# SCH_WINGLET_GNSS.net
KiCad netlist of a schematic drawn in Altium Designer
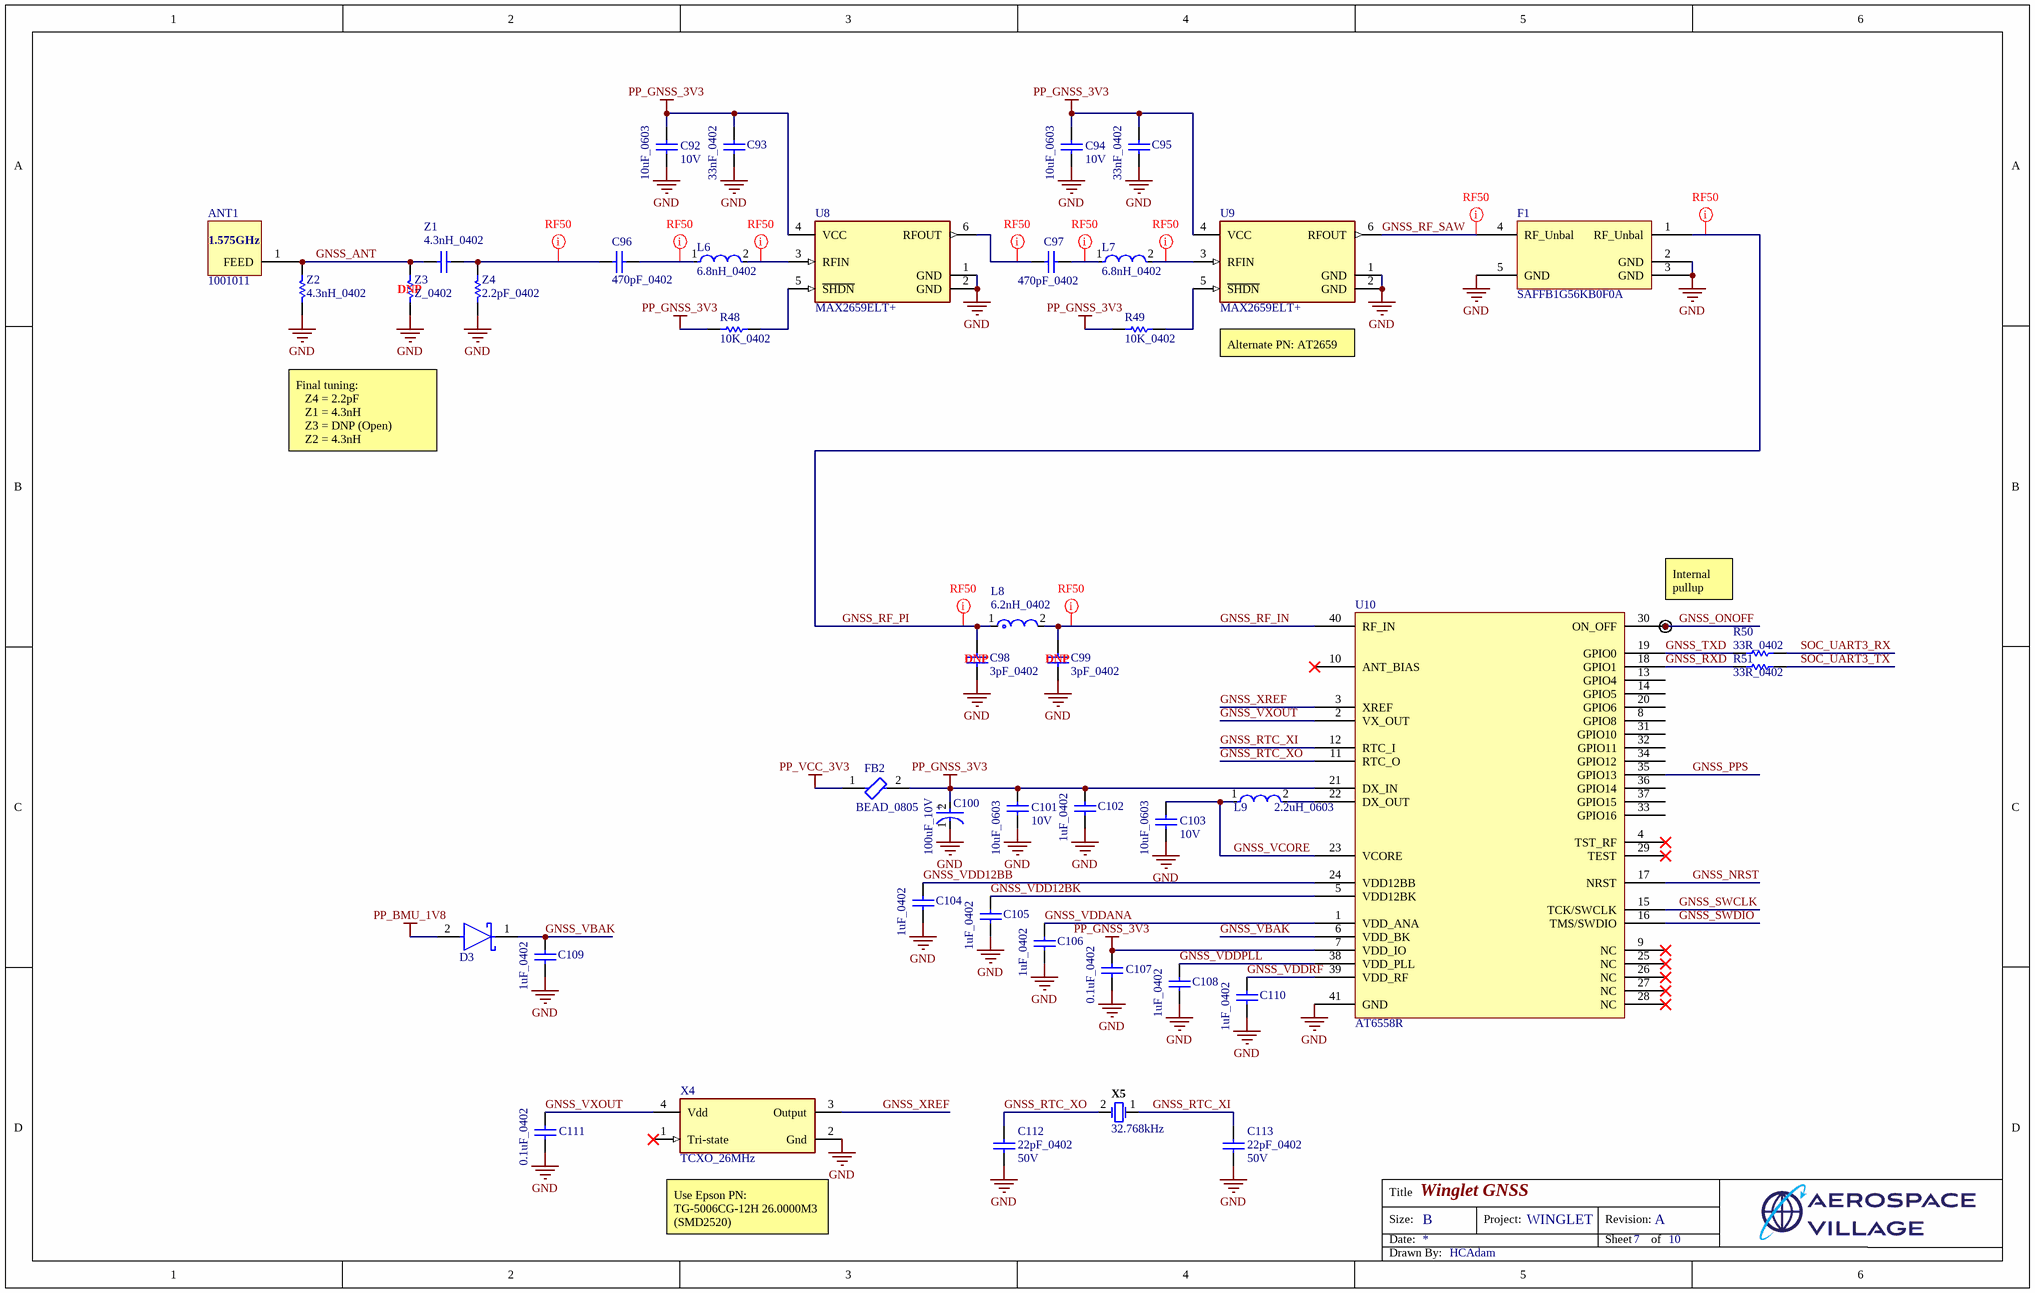
[diagram p0: SCH_WINGLET_GNSS.SchDoc]

(export (version "E")
  (design (tool "Eeschema 10.0.6"))
  (components
    (comp (ref "ANT1")
      (value "1001011")
      (footprint "ANT1001011")
      (libsource (lib "DCAV32_WINGLET_SCHLIB") (part "1001011"))
    )
    (comp (ref "C92")
      (value "10uF_0603")
      (footprint "CAPC1609X100X15NL20")
      (fields
        (field (name "PART NUMBER") "TACL106M006XTA")
        (field (name "MANUFACTURER") "AVX Interconnect / Elco")
        (field (name "VOLTAGE RATING") "10V")
      )
      (libsource (lib "Altium Content Vault") (part "CAP"))
    )
    (comp (ref "C93")
      (value "33nF_0402")
      (footprint "CAPC1005X56X25NL10T15")
      (libsource (lib "Altium Content Vault") (part "CAP"))
    )
    (comp (ref "C94")
      (value "10uF_0603")
      (footprint "CAPC1609X100X15NL20")
      (fields
        (field (name "PART NUMBER") "TACL106M006XTA")
        (field (name "MANUFACTURER") "AVX Interconnect / Elco")
        (field (name "VOLTAGE RATING") "10V")
      )
      (libsource (lib "Altium Content Vault") (part "CAP"))
    )
    (comp (ref "C95")
      (value "33nF_0402")
      (footprint "CAPC1005X56X25NL10T15")
      (libsource (lib "Altium Content Vault") (part "CAP"))
    )
    (comp (ref "C96")
      (value "470pF_0402")
      (footprint "CAPC1005X56X25NL10T15")
      (libsource (lib "Altium Content Vault") (part "CAP"))
    )
    (comp (ref "C97")
      (value "470pF_0402")
      (footprint "CAPC1005X56X25NL10T15")
      (libsource (lib "Altium Content Vault") (part "CAP"))
    )
    (comp (ref "C98")
      (value "3pF_0402")
      (footprint "CAPC1005X55X25NL05T10")
      (description "GRM1555C1H3R0BA01D")
      (fields (field (name "MANUFACTURER") "Murata") (field (name "DNP") "DNP"))
      (libsource (lib "Altium Content Vault") (part "CAP"))
    )
    (comp (ref "C99")
      (value "3pF_0402")
      (footprint "CAPC1005X55X25NL05T10")
      (description "GRM1555C1H3R0BA01D")
      (fields (field (name "MANUFACTURER") "Murata") (field (name "DNP") "DNP"))
      (libsource (lib "Altium Content Vault") (part "CAP"))
    )
    (comp (ref "C100")
      (value "100uF_10V")
      (footprint "FP-TAJB-MFG")
      (description "100uF 10V ±10% 1.7Ω SMD CASE-B (3528) Tantalum Capacitor")
      (fields (field (name "VOLTAGE") "6.3V") (field (name "TOLERANCE") "10%"))
      (libsource (lib "Altium Content Vault") (part "203bc49f2ac43e59fd269a8c329ed05"))
    )
    (comp (ref "C101")
      (value "10uF_0603")
      (footprint "CAPC1609X100X15NL20")
      (fields
        (field (name "PART NUMBER") "TACL106M006XTA")
        (field (name "MANUFACTURER") "AVX Interconnect / Elco")
        (field (name "VOLTAGE RATING") "10V")
      )
      (libsource (lib "Altium Content Vault") (part "CAP"))
    )
    (comp (ref "C102")
      (value "1uF_0402")
      (footprint "CAPC1005X55X25NL5T10")
      (fields (field (name "TOLERANCE") "10%") (field (name "PARTNUMBER") "GRM155R60J105KE19D"))
      (libsource (lib "Altium Content Vault") (part "CAP-NP-2"))
    )
    (comp (ref "C103")
      (value "10uF_0603")
      (footprint "CAPC1609X100X15NL20")
      (fields
        (field (name "PART NUMBER") "TACL106M006XTA")
        (field (name "MANUFACTURER") "AVX Interconnect / Elco")
        (field (name "VOLTAGE RATING") "10V")
      )
      (libsource (lib "Altium Content Vault") (part "CAP"))
    )
    (comp (ref "C104")
      (value "1uF_0402")
      (footprint "CAPC1005X55X25NL5T10")
      (fields (field (name "TOLERANCE") "10%") (field (name "PARTNUMBER") "GRM155R60J105KE19D"))
      (libsource (lib "Altium Content Vault") (part "CAP-NP-2"))
    )
    (comp (ref "C105")
      (value "1uF_0402")
      (footprint "CAPC1005X55X25NL5T10")
      (fields (field (name "TOLERANCE") "10%") (field (name "PARTNUMBER") "GRM155R60J105KE19D"))
      (libsource (lib "Altium Content Vault") (part "CAP-NP-2"))
    )
    (comp (ref "C106")
      (value "1uF_0402")
      (footprint "CAPC1005X55X25NL5T10")
      (fields (field (name "TOLERANCE") "10%") (field (name "PARTNUMBER") "GRM155R60J105KE19D"))
      (libsource (lib "Altium Content Vault") (part "CAP-NP-2"))
    )
    (comp (ref "C107")
      (value "0.1uF_0402")
      (footprint "CAPC1005X56X25NL10T15")
      (description "04026D104KAT2A")
      (fields (field (name "MANUFACTURER") "AVX Interconnect / Elco"))
      (libsource (lib "Altium Content Vault") (part "CAP"))
    )
    (comp (ref "C108")
      (value "1uF_0402")
      (footprint "CAPC1005X55X25NL5T10")
      (fields (field (name "TOLERANCE") "10%") (field (name "PARTNUMBER") "GRM155R60J105KE19D"))
      (libsource (lib "Altium Content Vault") (part "CAP-NP-2"))
    )
    (comp (ref "C109")
      (value "1uF_0402")
      (footprint "CAPC1005X55X25NL5T10")
      (fields (field (name "TOLERANCE") "10%") (field (name "PARTNUMBER") "GRM155R60J105KE19D"))
      (libsource (lib "Altium Content Vault") (part "CAP-NP-2"))
    )
    (comp (ref "C110")
      (value "1uF_0402")
      (footprint "CAPC1005X55X25NL5T10")
      (fields (field (name "TOLERANCE") "10%") (field (name "PARTNUMBER") "GRM155R60J105KE19D"))
      (libsource (lib "Altium Content Vault") (part "CAP-NP-2"))
    )
    (comp (ref "C111")
      (value "0.1uF_0402")
      (footprint "CAPC1005X56X25NL10T15")
      (description "04026D104KAT2A")
      (fields (field (name "MANUFACTURER") "AVX Interconnect / Elco"))
      (libsource (lib "Altium Content Vault") (part "CAP"))
    )
    (comp (ref "C112")
      (value "22pF_0402")
      (footprint "CAPC1005X56X25LL10T15")
      (description "04025A220JAT2A")
      (fields (field (name "MANUFACTURER") "AVX Interconnect / Elco") (field (name "VOLTAGE RATING") "50V"))
      (libsource (lib "Altium Content Vault") (part "CAP"))
    )
    (comp (ref "C113")
      (value "22pF_0402")
      (footprint "CAPC1005X56X25LL10T15")
      (description "04025A220JAT2A")
      (fields (field (name "MANUFACTURER") "AVX Interconnect / Elco") (field (name "VOLTAGE RATING") "50V"))
      (libsource (lib "Altium Content Vault") (part "CAP"))
    )
    (comp (ref "D3")
      (value "BAT54KFILM")
      (footprint "FP-SOD-523-MFG")
      (description "DIODE SCHOTTKY 40V 300MA SOD523")
      (fields
        (field (name "OCTOPART") "https://octopart.com/bat54kfilm-stmicroelectronics-39618022")
        (field (name "MANUFACTURER") "STMicroelectronics")
      )
      (libsource (lib "Altium Content Vault") (part "1d6ec82d83fb6aee721767c19dac4b9"))
    )
    (comp (ref "F1")
      (value "SAFFB1G56KB0F0A")
      (footprint "SAW80P110X50-5L")
      (description "SAW FILTER FOR GPS/GLONASS/BEIDOU2\r\n1561.10/1575.42/1602 MHz")
      (libsource (lib "DCAV32_WINGLET_SCHLIB") (part "SAFFB1G56KB0F0A"))
    )
    (comp (ref "FB2")
      (value "BEAD_0805")
      (footprint "FP-BLM21-0_2-t0_85-e0_5-IPC_B")
      (description "Chip Ferrite Bead, 0805, 150Ω @ 100MHz, 0.09Ω, 25%, 1A")
      (fields (field (name "TOLERANCE") "25%"))
      (libsource (lib "Altium Content Vault") (part "5f30dd21d616792df468990f7003faa"))
    )
    (comp (ref "L6")
      (value "6.8nH_0402")
      (footprint "FP-LQW15AN_00-W0_6-0_1-MFG")
      (description "Wire Wound RF Inductor 6.8nH ±3% 700mA 0.09Ω 0402 (1005)\r\nLQW15AN6N8H00D")
      (fields (field (name "TOLERANCE") "3%"))
      (libsource (lib "Altium Content Vault") (part "725321dda6339637d4d059423bc1c3c"))
    )
    (comp (ref "L7")
      (value "6.8nH_0402")
      (footprint "FP-LQW15AN_00-W0_6-0_1-MFG")
      (description "Wire Wound RF Inductor 6.8nH ±3% 700mA 0.09Ω 0402 (1005)\r\nLQW15AN6N8H00D")
      (fields (field (name "TOLERANCE") "3%"))
      (libsource (lib "Altium Content Vault") (part "725321dda6339637d4d059423bc1c3c"))
    )
    (comp (ref "L8")
      (value "6.2nH_0402")
      (footprint "FP-LQG15HH_02-IPC_C")
      (description "Multilayer type RF Inductor 6.2nH ±0.3nH 0.19Ω 600mA 0402\r\nLQG15HN6N2S02D")
      (libsource (lib "Altium Content Vault") (part "4cc4b267dca4c8e51f7102f422741d8"))
    )
    (comp (ref "L9")
      (value "2.2uH_0603")
      (footprint "FP-MLZ1608-IPC_C")
      (description "Shielded Multilayer Inductor 2.2uH ±20% 500mA 234mΩ SMD 0603\r\nMLZ1608N2R2LT000")
      (fields (field (name "TOLERANCE") "20%"))
      (libsource (lib "Altium Content Vault") (part "725321dda6339637d4d059423bc1c3c"))
    )
    (comp (ref "R48")
      (value "10K_0402")
      (footprint "RESC1005X40X25NL05T05")
      (fields (field (name "TOLERANCE") "1%") (field (name "MANUFACTURER") "Panasonic"))
      (libsource (lib "Altium Content Vault") (part "RES-2"))
    )
    (comp (ref "R49")
      (value "10K_0402")
      (footprint "RESC1005X40X25NL05T05")
      (fields (field (name "TOLERANCE") "1%") (field (name "MANUFACTURER") "Panasonic"))
      (libsource (lib "Altium Content Vault") (part "RES-2"))
    )
    (comp (ref "R50")
      (value "33R_0402")
      (footprint "RESC1005X40X25NL05T05")
      (description "ERJ2RKF33R0X")
      (fields (field (name "MANUFACTURER") "Panasonic"))
      (libsource (lib "Altium Content Vault") (part "RES"))
    )
    (comp (ref "R51")
      (value "33R_0402")
      (footprint "RESC1005X40X25NL05T05")
      (description "ERJ2RKF33R0X")
      (fields (field (name "MANUFACTURER") "Panasonic"))
      (libsource (lib "Altium Content Vault") (part "RES"))
    )
    (comp (ref "TP27")
      (value "TESTPOINT")
      (footprint "TESTPOINT-0.7MM-SINGLE-LAYER")
      (description "TESTPOINT SINGLE LAYER 0.7MM")
      (libsource (lib "DCAV32_WINGLET_SCHLIB") (part "TP_07"))
    )
    (comp (ref "U8")
      (value "MAX2659ELT+")
      (footprint "FP-L611-2-MFG")
      (description "GPS Amp Single Low Noise 1.75GHz 3.6V 6-Pin UDFN")
      (libsource (lib "Altium Content Vault") (part "fca23d189b6920f08195121cb41012b"))
    )
    (comp (ref "U9")
      (value "MAX2659ELT+")
      (footprint "FP-L611-2-MFG")
      (description "GPS Amp Single Low Noise 1.75GHz 3.6V 6-Pin UDFN")
      (libsource (lib "Altium Content Vault") (part "fca23d189b6920f08195121cb41012b"))
    )
    (comp (ref "U10")
      (value "AT6558R")
      (footprint "QFN40P500X500X90_HS-41N")
      (description "GNSS/BDS Satellite Positioning SOC")
      (libsource (lib "DCAV32_WINGLET_SCHLIB") (part "AT6558R"))
    )
    (comp (ref "X4")
      (value "TCXO_26MHz")
      (footprint "FP-ECS-TXO-2520-MFG")
      (description "XTAL OSC TCXO 25.0000MHZ HCMOS\r\n!!! SUBSTITUTE !!!")
      (libsource (lib "Altium Content Vault") (part "04cd953f3cf158082f8c09fbdb924ef"))
    )
    (comp (ref "X5")
      (value "32.768kHz")
      (footprint "ABRA-ABS07_A_V")
      (fields (field (name "MANUFACTURER") "Abracon") (field (name "TOLERANCE") "20ppm"))
      (libsource (lib "Altium Content Vault") (part "XTAL-1-2-2"))
    )
    (comp (ref "Z1")
      (value "4.3nH_0402")
      (footprint "CAPC1006X50X20NL10T10")
      (description "04023J1R6ABSTR")
      (fields (field (name "MANUFACTURER") "AVX Interconnect / Elco"))
      (libsource (lib "Altium Content Vault") (part "CAP"))
    )
    (comp (ref "Z2")
      (value "4.3nH_0402")
      (footprint "RESC1005X40X25NL05T05")
      (fields (field (name "TOLERANCE") "1%") (field (name "MANUFACTURER") "Panasonic"))
      (libsource (lib "Altium Content Vault") (part "RES-2"))
    )
    (comp (ref "Z3")
      (value "Z_0402")
      (footprint "RESC1005X40X25NL05T05")
      (fields
        (field (name "TOLERANCE") "1%")
        (field (name "MANUFACTURER") "Panasonic")
        (field (name "DNP") "DNP")
      )
      (libsource (lib "Altium Content Vault") (part "RES-2"))
    )
    (comp (ref "Z4")
      (value "2.2pF_0402")
      (footprint "RESC1005X40X25NL05T05")
      (fields (field (name "TOLERANCE") "1%") (field (name "MANUFACTURER") "Panasonic"))
      (libsource (lib "Altium Content Vault") (part "RES-2"))
    )
  )
  (nets
    (net (code "1") (name "/GNSS_ANT") (class "Default")
      (node (ref "ANT1") (pin "1") (pinfunction "FEED_1") (pintype "passive"))
      (node (ref "Z1") (pin "2") (pinfunction "2_2") (pintype "passive"))
      (node (ref "Z2") (pin "2") (pinfunction "2_2") (pintype "passive"))
      (node (ref "Z3") (pin "2") (pinfunction "2_2") (pintype "passive"))
    )
    (net (code "2") (name "/GNSS_NRST") (class "Default")
      (node (ref "U10") (pin "17") (pinfunction "NRST_17") (pintype "passive"))
    )
    (net (code "3") (name "/GNSS_ONOFF") (class "Default")
      (node (ref "TP27") (pin "1") (pinfunction "1_1") (pintype "passive"))
      (node (ref "U10") (pin "30") (pinfunction "ON_OFF_30") (pintype "passive"))
    )
    (net (code "4") (name "/GNSS_PPS") (class "Default")
      (node (ref "U10") (pin "35") (pinfunction "GPIO13_35") (pintype "passive"))
    )
    (net (code "5") (name "/GNSS_RF_IN") (class "Default")
      (node (ref "C99") (pin "2") (pinfunction "2_2") (pintype "passive"))
      (node (ref "L8") (pin "2") (pinfunction "2_2") (pintype "passive"))
      (node (ref "U10") (pin "40") (pinfunction "RF_IN_40") (pintype "passive"))
    )
    (net (code "6") (name "/GNSS_RF_PI") (class "Default")
      (node (ref "C98") (pin "2") (pinfunction "2_2") (pintype "passive"))
      (node (ref "F1") (pin "1") (pinfunction "RF_Unbal_1") (pintype "passive"))
      (node (ref "L8") (pin "1") (pinfunction "1_1") (pintype "passive"))
    )
    (net (code "7") (name "/GNSS_RF_SAW") (class "Default")
      (node (ref "F1") (pin "4") (pinfunction "RF_Unbal_4") (pintype "passive"))
      (node (ref "U9") (pin "6") (pinfunction "RFOUT_6") (pintype "output"))
    )
    (net (code "8") (name "/GNSS_RTC_XI") (class "Default")
      (node (ref "C113") (pin "2") (pinfunction "2_2") (pintype "passive"))
      (node (ref "U10") (pin "12") (pinfunction "RTC_I_12") (pintype "passive"))
      (node (ref "X5") (pin "1") (pinfunction "1_1") (pintype "passive"))
    )
    (net (code "9") (name "/GNSS_RTC_XO") (class "Default")
      (node (ref "C112") (pin "2") (pinfunction "2_2") (pintype "passive"))
      (node (ref "U10") (pin "11") (pinfunction "RTC_O_11") (pintype "passive"))
      (node (ref "X5") (pin "2") (pinfunction "2_2") (pintype "passive"))
    )
    (net (code "10") (name "/GNSS_RXD") (class "Default")
      (node (ref "R51") (pin "1") (pinfunction "1_1") (pintype "passive"))
      (node (ref "U10") (pin "18") (pinfunction "GPIO1_18") (pintype "passive"))
    )
    (net (code "11") (name "/GNSS_SWCLK") (class "Default")
      (node (ref "U10") (pin "15") (pinfunction "TCK/SWCLK_15") (pintype "passive"))
    )
    (net (code "12") (name "/GNSS_SWDIO") (class "Default")
      (node (ref "U10") (pin "16") (pinfunction "TMS/SWDIO_16") (pintype "passive"))
    )
    (net (code "13") (name "/GNSS_TXD") (class "Default")
      (node (ref "R50") (pin "1") (pinfunction "1_1") (pintype "passive"))
      (node (ref "U10") (pin "19") (pinfunction "GPIO0_19") (pintype "passive"))
    )
    (net (code "14") (name "/GNSS_VBAK") (class "Default")
      (node (ref "C109") (pin "2") (pinfunction "2_2") (pintype "passive"))
      (node (ref "D3") (pin "1") (pinfunction "C_1") (pintype "passive"))
      (node (ref "U10") (pin "6") (pinfunction "VDD_BK_6") (pintype "passive"))
    )
    (net (code "15") (name "/GNSS_VCORE") (class "Default")
      (node (ref "C103") (pin "2") (pinfunction "2_2") (pintype "passive"))
      (node (ref "L9") (pin "1") (pinfunction "1_1") (pintype "passive"))
      (node (ref "U10") (pin "23") (pinfunction "VCORE_23") (pintype "passive"))
    )
    (net (code "16") (name "/GNSS_VDD12BB") (class "Default")
      (node (ref "C104") (pin "2") (pinfunction "2_2") (pintype "passive"))
      (node (ref "U10") (pin "24") (pinfunction "VDD12BB_24") (pintype "passive"))
    )
    (net (code "17") (name "/GNSS_VDD12BK") (class "Default")
      (node (ref "C105") (pin "2") (pinfunction "2_2") (pintype "passive"))
      (node (ref "U10") (pin "5") (pinfunction "VDD12BK_5") (pintype "passive"))
    )
    (net (code "18") (name "/GNSS_VDDANA") (class "Default")
      (node (ref "C106") (pin "2") (pinfunction "2_2") (pintype "passive"))
      (node (ref "U10") (pin "1") (pinfunction "VDD_ANA_1") (pintype "passive"))
    )
    (net (code "19") (name "/GNSS_VDDPLL") (class "Default")
      (node (ref "C108") (pin "2") (pinfunction "2_2") (pintype "passive"))
      (node (ref "U10") (pin "38") (pinfunction "VDD_PLL_38") (pintype "passive"))
    )
    (net (code "20") (name "/GNSS_VDDRF") (class "Default")
      (node (ref "C110") (pin "2") (pinfunction "2_2") (pintype "passive"))
      (node (ref "U10") (pin "39") (pinfunction "VDD_RF_39") (pintype "passive"))
    )
    (net (code "21") (name "/GNSS_VXOUT") (class "Default")
      (node (ref "C111") (pin "2") (pinfunction "2_2") (pintype "passive"))
      (node (ref "U10") (pin "2") (pinfunction "VX_OUT_2") (pintype "passive"))
      (node (ref "X4") (pin "4") (pinfunction "Vdd_4") (pintype "power_in"))
    )
    (net (code "22") (name "/GNSS_XREF") (class "Default")
      (node (ref "U10") (pin "3") (pinfunction "XREF_3") (pintype "passive"))
      (node (ref "X4") (pin "3") (pinfunction "Output_3") (pintype "tri_state"))
    )
    (net (code "23") (name "/SOC_UART3_RX") (class "Default")
      (node (ref "R50") (pin "2") (pinfunction "2_2") (pintype "passive"))
    )
    (net (code "24") (name "/SOC_UART3_TX") (class "Default")
      (node (ref "R51") (pin "2") (pinfunction "2_2") (pintype "passive"))
    )
    (net (code "25") (name "GND") (class "Default")
      (node (ref "C100") (pin "1") (pinfunction "C_1") (pintype "passive"))
      (node (ref "C101") (pin "1") (pinfunction "1_1") (pintype "passive"))
      (node (ref "C102") (pin "1") (pinfunction "1_1") (pintype "passive"))
      (node (ref "C103") (pin "1") (pinfunction "1_1") (pintype "passive"))
      (node (ref "C104") (pin "1") (pinfunction "1_1") (pintype "passive"))
      (node (ref "C105") (pin "1") (pinfunction "1_1") (pintype "passive"))
      (node (ref "C106") (pin "1") (pinfunction "1_1") (pintype "passive"))
      (node (ref "C107") (pin "1") (pinfunction "1_1") (pintype "passive"))
      (node (ref "C108") (pin "1") (pinfunction "1_1") (pintype "passive"))
      (node (ref "C109") (pin "1") (pinfunction "1_1") (pintype "passive"))
      (node (ref "C110") (pin "1") (pinfunction "1_1") (pintype "passive"))
      (node (ref "C111") (pin "1") (pinfunction "1_1") (pintype "passive"))
      (node (ref "C112") (pin "1") (pinfunction "1_1") (pintype "passive"))
      (node (ref "C113") (pin "1") (pinfunction "1_1") (pintype "passive"))
      (node (ref "C92") (pin "1") (pinfunction "1_1") (pintype "passive"))
      (node (ref "C93") (pin "2") (pinfunction "2_2") (pintype "passive"))
      (node (ref "C94") (pin "1") (pinfunction "1_1") (pintype "passive"))
      (node (ref "C95") (pin "2") (pinfunction "2_2") (pintype "passive"))
      (node (ref "C98") (pin "1") (pinfunction "1_1") (pintype "passive"))
      (node (ref "C99") (pin "1") (pinfunction "1_1") (pintype "passive"))
      (node (ref "F1") (pin "2") (pinfunction "GND_2") (pintype "passive"))
      (node (ref "F1") (pin "3") (pinfunction "GND_3") (pintype "passive"))
      (node (ref "F1") (pin "5") (pinfunction "GND_5") (pintype "passive"))
      (node (ref "U10") (pin "41") (pinfunction "GND_41") (pintype "passive"))
      (node (ref "U8") (pin "1") (pinfunction "GND_1") (pintype "power_in"))
      (node (ref "U8") (pin "2") (pinfunction "GND_2") (pintype "power_in"))
      (node (ref "U9") (pin "1") (pinfunction "GND_1") (pintype "power_in"))
      (node (ref "U9") (pin "2") (pinfunction "GND_2") (pintype "power_in"))
      (node (ref "X4") (pin "2") (pinfunction "Gnd_2") (pintype "power_in"))
      (node (ref "Z2") (pin "1") (pinfunction "1_1") (pintype "passive"))
      (node (ref "Z3") (pin "1") (pinfunction "1_1") (pintype "passive"))
      (node (ref "Z4") (pin "1") (pinfunction "1_1") (pintype "passive"))
    )
    (net (code "26") (name "Net-(C96-Pad1)") (class "Default")
      (node (ref "C96") (pin "1") (pinfunction "1_1") (pintype "passive"))
      (node (ref "L6") (pin "1") (pinfunction "1_1") (pintype "passive"))
    )
    (net (code "27") (name "Net-(C96-Pad2)") (class "Default")
      (node (ref "C96") (pin "2") (pinfunction "2_2") (pintype "passive"))
      (node (ref "Z1") (pin "1") (pinfunction "1_1") (pintype "passive"))
      (node (ref "Z4") (pin "2") (pinfunction "2_2") (pintype "passive"))
    )
    (net (code "28") (name "Net-(C97-Pad1)") (class "Default")
      (node (ref "C97") (pin "1") (pinfunction "1_1") (pintype "passive"))
      (node (ref "L7") (pin "1") (pinfunction "1_1") (pintype "passive"))
    )
    (net (code "29") (name "Net-(U8-RFIN)") (class "Default")
      (node (ref "L6") (pin "2") (pinfunction "2_2") (pintype "passive"))
      (node (ref "U8") (pin "3") (pinfunction "RFIN_3") (pintype "input"))
    )
    (net (code "30") (name "Net-(U8-RFOUT)") (class "Default")
      (node (ref "C97") (pin "2") (pinfunction "2_2") (pintype "passive"))
      (node (ref "U8") (pin "6") (pinfunction "RFOUT_6") (pintype "output"))
    )
    (net (code "31") (name "Net-(U8-~{SHDN})") (class "Default")
      (node (ref "R48") (pin "2") (pinfunction "2_2") (pintype "passive"))
      (node (ref "U8") (pin "5") (pinfunction "~{SHDN}_5") (pintype "input"))
    )
    (net (code "32") (name "Net-(U9-RFIN)") (class "Default")
      (node (ref "L7") (pin "2") (pinfunction "2_2") (pintype "passive"))
      (node (ref "U9") (pin "3") (pinfunction "RFIN_3") (pintype "input"))
    )
    (net (code "33") (name "Net-(U9-~{SHDN})") (class "Default")
      (node (ref "R49") (pin "2") (pinfunction "2_2") (pintype "passive"))
      (node (ref "U9") (pin "5") (pinfunction "~{SHDN}_5") (pintype "input"))
    )
    (net (code "34") (name "Net-(U10-DX_OUT)") (class "Default")
      (node (ref "L9") (pin "2") (pinfunction "2_2") (pintype "passive"))
      (node (ref "U10") (pin "22") (pinfunction "DX_OUT_22") (pintype "passive"))
    )
    (net (code "35") (name "PP_BMU_1V8") (class "Default")
      (node (ref "D3") (pin "2") (pinfunction "A_2") (pintype "passive"))
    )
    (net (code "36") (name "PP_GNSS_3V3") (class "Default")
      (node (ref "C100") (pin "2") (pinfunction "A_2") (pintype "passive"))
      (node (ref "C101") (pin "2") (pinfunction "2_2") (pintype "passive"))
      (node (ref "C102") (pin "2") (pinfunction "2_2") (pintype "passive"))
      (node (ref "C107") (pin "2") (pinfunction "2_2") (pintype "passive"))
      (node (ref "C92") (pin "2") (pinfunction "2_2") (pintype "passive"))
      (node (ref "C93") (pin "1") (pinfunction "1_1") (pintype "passive"))
      (node (ref "C94") (pin "2") (pinfunction "2_2") (pintype "passive"))
      (node (ref "C95") (pin "1") (pinfunction "1_1") (pintype "passive"))
      (node (ref "FB2") (pin "2") (pinfunction "2_2") (pintype "passive"))
      (node (ref "R48") (pin "1") (pinfunction "1_1") (pintype "passive"))
      (node (ref "R49") (pin "1") (pinfunction "1_1") (pintype "passive"))
      (node (ref "U10") (pin "21") (pinfunction "DX_IN_21") (pintype "passive"))
      (node (ref "U10") (pin "7") (pinfunction "VDD_IO_7") (pintype "passive"))
      (node (ref "U8") (pin "4") (pinfunction "VCC_4") (pintype "power_in"))
      (node (ref "U9") (pin "4") (pinfunction "VCC_4") (pintype "power_in"))
    )
    (net (code "37") (name "PP_VCC_3V3") (class "Default")
      (node (ref "FB2") (pin "1") (pinfunction "1_1") (pintype "passive"))
    )
    (net (code "38") (name "unconnected-(U10-ANT_BIAS-Pad10)") (class "Default")
      (node (ref "U10") (pin "10") (pinfunction "ANT_BIAS_10") (pintype "passive+no_connect"))
    )
    (net (code "39") (name "unconnected-(U10-GPIO4-Pad13)") (class "Default")
      (node (ref "U10") (pin "13") (pinfunction "GPIO4_13") (pintype "passive"))
    )
    (net (code "40") (name "unconnected-(U10-GPIO5-Pad14)") (class "Default")
      (node (ref "U10") (pin "14") (pinfunction "GPIO5_14") (pintype "passive"))
    )
    (net (code "41") (name "unconnected-(U10-GPIO6-Pad20)") (class "Default")
      (node (ref "U10") (pin "20") (pinfunction "GPIO6_20") (pintype "passive"))
    )
    (net (code "42") (name "unconnected-(U10-GPIO8-Pad8)") (class "Default")
      (node (ref "U10") (pin "8") (pinfunction "GPIO8_8") (pintype "passive"))
    )
    (net (code "43") (name "unconnected-(U10-GPIO10-Pad31)") (class "Default")
      (node (ref "U10") (pin "31") (pinfunction "GPIO10_31") (pintype "passive"))
    )
    (net (code "44") (name "unconnected-(U10-GPIO11-Pad32)") (class "Default")
      (node (ref "U10") (pin "32") (pinfunction "GPIO11_32") (pintype "passive"))
    )
    (net (code "45") (name "unconnected-(U10-GPIO12-Pad34)") (class "Default")
      (node (ref "U10") (pin "34") (pinfunction "GPIO12_34") (pintype "passive"))
    )
    (net (code "46") (name "unconnected-(U10-GPIO14-Pad36)") (class "Default")
      (node (ref "U10") (pin "36") (pinfunction "GPIO14_36") (pintype "passive"))
    )
    (net (code "47") (name "unconnected-(U10-GPIO15-Pad37)") (class "Default")
      (node (ref "U10") (pin "37") (pinfunction "GPIO15_37") (pintype "passive"))
    )
    (net (code "48") (name "unconnected-(U10-GPIO16-Pad33)") (class "Default")
      (node (ref "U10") (pin "33") (pinfunction "GPIO16_33") (pintype "passive"))
    )
    (net (code "49") (name "unconnected-(U10-NC-Pad9)") (class "Default")
      (node (ref "U10") (pin "9") (pinfunction "NC_9") (pintype "passive+no_connect"))
    )
    (net (code "50") (name "unconnected-(U10-NC-Pad25)") (class "Default")
      (node (ref "U10") (pin "25") (pinfunction "NC_25") (pintype "passive+no_connect"))
    )
    (net (code "51") (name "unconnected-(U10-NC-Pad26)") (class "Default")
      (node (ref "U10") (pin "26") (pinfunction "NC_26") (pintype "passive+no_connect"))
    )
    (net (code "52") (name "unconnected-(U10-NC-Pad27)") (class "Default")
      (node (ref "U10") (pin "27") (pinfunction "NC_27") (pintype "passive+no_connect"))
    )
    (net (code "53") (name "unconnected-(U10-NC-Pad28)") (class "Default")
      (node (ref "U10") (pin "28") (pinfunction "NC_28") (pintype "passive+no_connect"))
    )
    (net (code "54") (name "unconnected-(U10-TEST-Pad29)") (class "Default")
      (node (ref "U10") (pin "29") (pinfunction "TEST_29") (pintype "passive+no_connect"))
    )
    (net (code "55") (name "unconnected-(U10-TST_RF-Pad4)") (class "Default")
      (node (ref "U10") (pin "4") (pinfunction "TST_RF_4") (pintype "passive+no_connect"))
    )
    (net (code "56") (name "unconnected-(X4-Tri-state-Pad1)") (class "Default")
      (node (ref "X4") (pin "1") (pinfunction "Tri-state_1") (pintype "input+no_connect"))
    )
  )
)
